# 09_Misc.net
KiCad netlist of a schematic drawn in Altium Designer
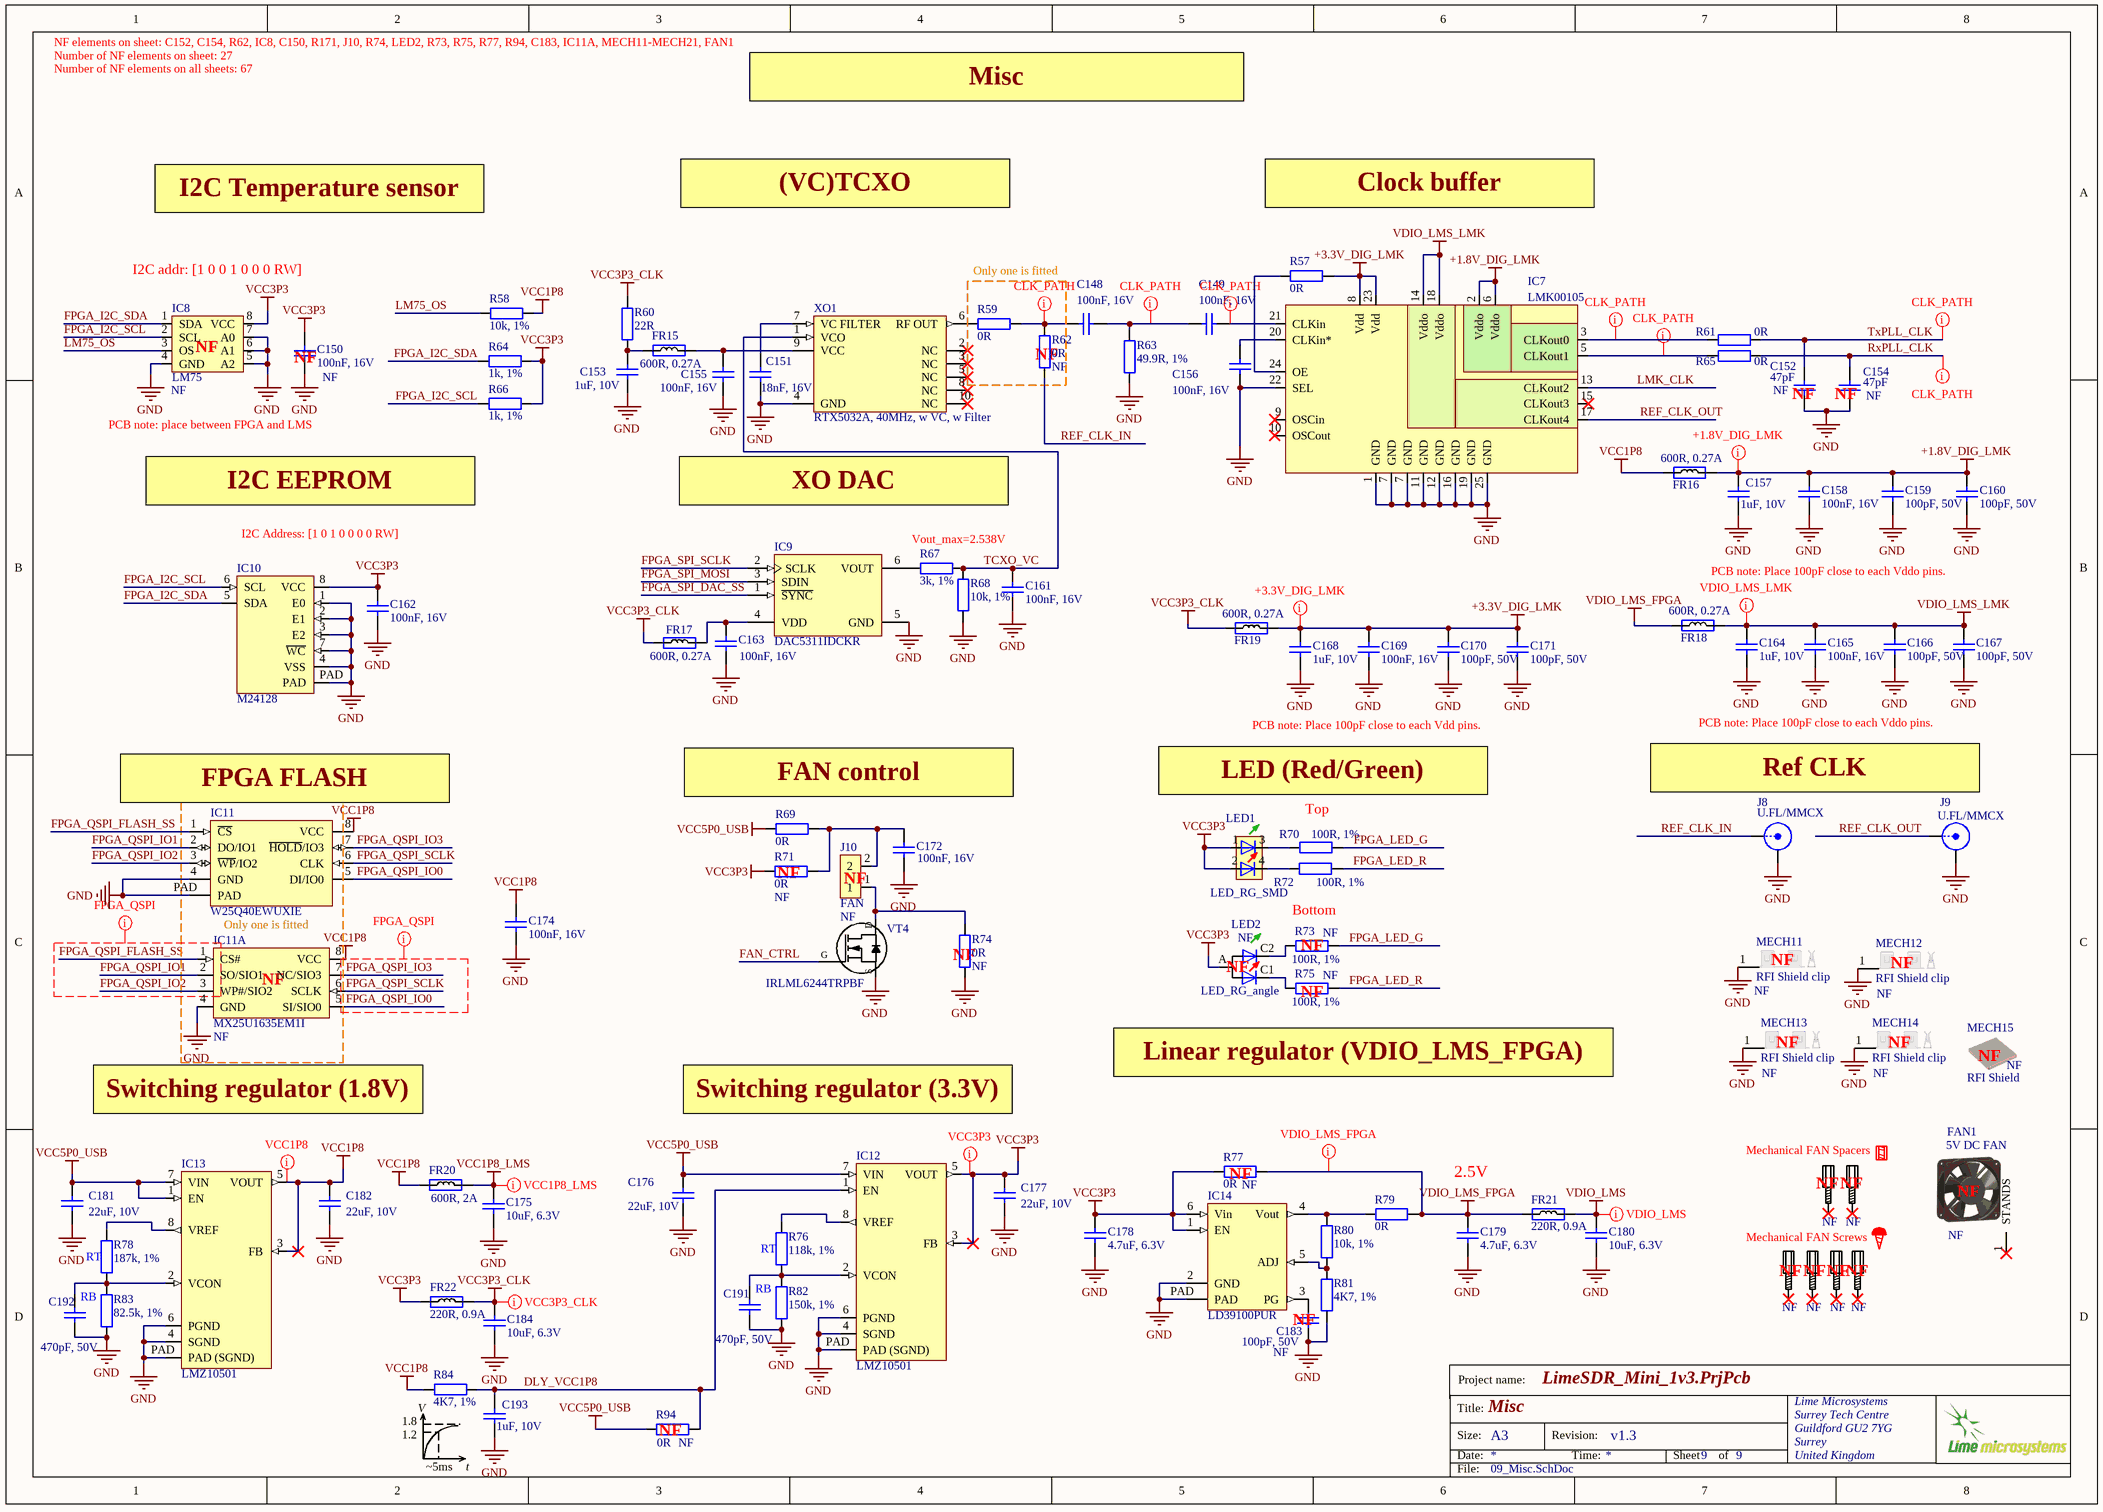
[diagram p0: 09_Misc.SchDoc]

(export (version "E")
  (design (tool "Eeschema 10.0.6"))
  (components
    (comp (ref "C148")
      (value "100nF, 16V")
      (footprint "CAP0402")
      (fields
        (field (name "MANUFACTURER") "Murata Electronics")
        (field (name "TOLERANCE") "10 %")
        (field (name "MANUFACTURER PART NUMBER") "GRM155R71C104KA88D")
      )
      (libsource (lib "LimeMicroAltiumLib_schLib") (part "Cap_0402"))
    )
    (comp (ref "C149")
      (value "100nF, 16V")
      (footprint "CAP0402")
      (fields
        (field (name "MANUFACTURER") "Murata Electronics")
        (field (name "TOLERANCE") "10 %")
        (field (name "MANUFACTURER PART NUMBER") "GRM155R71C104KA88D")
      )
      (libsource (lib "LimeMicroAltiumLib_schLib") (part "Cap_0402"))
    )
    (comp (ref "C150")
      (value "100nF, 16V")
      (footprint "CAP0402")
      (fields
        (field (name "TOLERANCE") "10 %")
        (field (name "MANUFACTURER") "Murata Electronics")
        (field (name "MANUFACTURER PART NUMBER") "GRM155R71C104KA88D")
        (field (name "ASSEMBLY INFO") "NF")
      )
      (libsource (lib "LimeFPGAboard_schLib") (part "Cap_0603"))
    )
    (comp (ref "C151")
      (value "18nF, 16V")
      (footprint "CAP0402")
      (fields (field (name "MANUFACTURER") "Yageo") (field (name "TOLERANCE") "±10%"))
      (libsource (lib "LimeMicroAltiumLib_schLib") (part "Cap_0402"))
    )
    (comp (ref "C152")
      (value "47pF")
      (footprint "CAP0402")
      (fields
        (field (name "TOLERANCE") "±1%")
        (field (name "MANUFACTURER") "TDK Corporation")
        (field (name "ASSEMBLY INFO") "NF")
      )
      (libsource (lib "LimeMicroAltiumLib_schLib") (part "Cap_0402"))
    )
    (comp (ref "C153")
      (value "1uF, 10V")
      (footprint "CAP0402")
      (fields (field (name "MANUFACTURER") "TDK"))
      (libsource (lib "LimeMicroAltiumLib_schLib") (part "Cap_0402"))
    )
    (comp (ref "C154")
      (value "47pF")
      (footprint "CAP0402")
      (fields
        (field (name "TOLERANCE") "±1%")
        (field (name "MANUFACTURER") "TDK Corporation")
        (field (name "ASSEMBLY INFO") "NF")
      )
      (libsource (lib "LimeMicroAltiumLib_schLib") (part "Cap_0402"))
    )
    (comp (ref "C155")
      (value "100nF, 16V")
      (footprint "CAP0402")
      (fields
        (field (name "MANUFACTURER") "Murata Electronics")
        (field (name "TOLERANCE") "10 %")
        (field (name "MANUFACTURER PART NUMBER") "GRM155R71C104KA88D")
      )
      (libsource (lib "LimeMicroAltiumLib_schLib") (part "Cap_0402"))
    )
    (comp (ref "C156")
      (value "100nF, 16V")
      (footprint "CAP0402")
      (fields
        (field (name "MANUFACTURER") "Murata Electronics")
        (field (name "TOLERANCE") "10 %")
        (field (name "MANUFACTURER PART NUMBER") "GRM155R71C104KA88D")
      )
      (libsource (lib "LimeMicroAltiumLib_schLib") (part "Cap_0402"))
    )
    (comp (ref "C157")
      (value "1uF, 10V")
      (footprint "CAP0402")
      (fields (field (name "MANUFACTURER") "TDK"))
      (libsource (lib "LimeMicroAltiumLib_schLib") (part "Cap_0402"))
    )
    (comp (ref "C158")
      (value "100nF, 16V")
      (footprint "CAP0402")
      (fields
        (field (name "MANUFACTURER") "Murata Electronics")
        (field (name "TOLERANCE") "10 %")
        (field (name "MANUFACTURER PART NUMBER") "GRM155R71C104KA88D")
      )
      (libsource (lib "LimeMicroAltiumLib_schLib") (part "Cap_0402"))
    )
    (comp (ref "C159")
      (value "100pF, 50V")
      (footprint "CAP0402")
      (fields (field (name "MANUFACTURER") "Yageo") (field (name "TOLERANCE") "±5%"))
      (libsource (lib "LimeMicroAltiumLib_schLib") (part "Cap_0402"))
    )
    (comp (ref "C160")
      (value "100pF, 50V")
      (footprint "CAP0402")
      (fields (field (name "MANUFACTURER") "Yageo") (field (name "TOLERANCE") "±5%"))
      (libsource (lib "LimeMicroAltiumLib_schLib") (part "Cap_0402"))
    )
    (comp (ref "C161")
      (value "100nF, 16V")
      (footprint "CAP0402")
      (fields
        (field (name "MANUFACTURER") "Murata Electronics")
        (field (name "TOLERANCE") "10 %")
        (field (name "MANUFACTURER PART NUMBER") "GRM155R71C104KA88D")
      )
      (libsource (lib "LimeMicroAltiumLib_schLib") (part "Cap_0402"))
    )
    (comp (ref "C162")
      (value "100nF, 16V")
      (footprint "CAP0402")
      (fields
        (field (name "TOLERANCE") "10 %")
        (field (name "MANUFACTURER") "Murata Electronics")
        (field (name "MANUFACTURER PART NUMBER") "GRM155R71C104KA88D")
      )
      (libsource (lib "LimeFPGAboard_schLib") (part "Cap_0603"))
    )
    (comp (ref "C163")
      (value "100nF, 16V")
      (footprint "CAP0402")
      (fields
        (field (name "TOLERANCE") "10 %")
        (field (name "MANUFACTURER") "Murata Electronics")
        (field (name "MANUFACTURER PART NUMBER") "GRM155R71C104KA88D")
      )
      (libsource (lib "LimeFPGAboard_schLib") (part "Cap_0603"))
    )
    (comp (ref "C164")
      (value "1uF, 10V")
      (footprint "CAP0402")
      (fields (field (name "MANUFACTURER") "TDK"))
      (libsource (lib "LimeMicroAltiumLib_schLib") (part "Cap_0402"))
    )
    (comp (ref "C165")
      (value "100nF, 16V")
      (footprint "CAP0402")
      (fields
        (field (name "MANUFACTURER") "Murata Electronics")
        (field (name "TOLERANCE") "10 %")
        (field (name "MANUFACTURER PART NUMBER") "GRM155R71C104KA88D")
      )
      (libsource (lib "LimeMicroAltiumLib_schLib") (part "Cap_0402"))
    )
    (comp (ref "C166")
      (value "100pF, 50V")
      (footprint "CAP0402")
      (fields (field (name "MANUFACTURER") "Yageo") (field (name "TOLERANCE") "±5%"))
      (libsource (lib "LimeMicroAltiumLib_schLib") (part "Cap_0402"))
    )
    (comp (ref "C167")
      (value "100pF, 50V")
      (footprint "CAP0402")
      (fields (field (name "MANUFACTURER") "Yageo") (field (name "TOLERANCE") "±5%"))
      (libsource (lib "LimeMicroAltiumLib_schLib") (part "Cap_0402"))
    )
    (comp (ref "C168")
      (value "1uF, 10V")
      (footprint "CAP0402")
      (fields (field (name "MANUFACTURER") "TDK"))
      (libsource (lib "LimeMicroAltiumLib_schLib") (part "Cap_0402"))
    )
    (comp (ref "C169")
      (value "100nF, 16V")
      (footprint "CAP0402")
      (fields
        (field (name "MANUFACTURER") "Murata Electronics")
        (field (name "TOLERANCE") "10 %")
        (field (name "MANUFACTURER PART NUMBER") "GRM155R71C104KA88D")
      )
      (libsource (lib "LimeMicroAltiumLib_schLib") (part "Cap_0402"))
    )
    (comp (ref "C170")
      (value "100pF, 50V")
      (footprint "CAP0402")
      (fields (field (name "MANUFACTURER") "Yageo") (field (name "TOLERANCE") "±5%"))
      (libsource (lib "LimeMicroAltiumLib_schLib") (part "Cap_0402"))
    )
    (comp (ref "C171")
      (value "100pF, 50V")
      (footprint "CAP0402")
      (fields (field (name "MANUFACTURER") "Yageo") (field (name "TOLERANCE") "±5%"))
      (libsource (lib "LimeMicroAltiumLib_schLib") (part "Cap_0402"))
    )
    (comp (ref "C172")
      (value "100nF, 16V")
      (footprint "CAP0402")
      (fields
        (field (name "TOLERANCE") "10 %")
        (field (name "MANUFACTURER") "Murata Electronics")
        (field (name "MANUFACTURER PART NUMBER") "GRM155R71C104KA88D")
      )
      (libsource (lib "LimeFPGAboard_schLib") (part "Cap_0603"))
    )
    (comp (ref "C174")
      (value "100nF, 16V")
      (footprint "CAP0402")
      (fields
        (field (name "TOLERANCE") "10 %")
        (field (name "MANUFACTURER") "Murata Electronics")
        (field (name "MANUFACTURER PART NUMBER") "GRM155R71C104KA88D")
      )
      (libsource (lib "LimeFPGAboard_schLib") (part "Cap_0603"))
    )
    (comp (ref "C175")
      (value "10uF, 6.3V")
      (footprint "CAP0603")
      (fields (field (name "TOLERANCE") "±20%") (field (name "MANUFACTURER") "Yageo"))
      (libsource (lib "LimeFPGAboard_schLib") (part "Cap_0603"))
    )
    (comp (ref "C176")
      (value "22uF, 10V")
      (footprint "CAP0603")
      (fields (field (name "TOLERANCE") "20 %") (field (name "MANUFACTURER") "TDK Corporation"))
      (libsource (lib "LimeFPGAboard_schLib") (part "Cap_0603"))
    )
    (comp (ref "C177")
      (value "22uF, 10V")
      (footprint "CAP0603")
      (fields (field (name "TOLERANCE") "20 %") (field (name "MANUFACTURER") "TDK Corporation"))
      (libsource (lib "LimeFPGAboard_schLib") (part "Cap_0603"))
    )
    (comp (ref "C178")
      (value "4.7uF, 6.3V")
      (footprint "CAP0402")
      (fields
        (field (name "MANUFACTURER") "Murata Electronics North America")
        (field (name "TOLERANCE") "±20%")
      )
      (libsource (lib "LimeMicroAltiumLib_schLib") (part "Cap_0402"))
    )
    (comp (ref "C179")
      (value "4.7uF, 6.3V")
      (footprint "CAP0402")
      (fields
        (field (name "MANUFACTURER") "Murata Electronics North America")
        (field (name "TOLERANCE") "±20%")
      )
      (libsource (lib "LimeMicroAltiumLib_schLib") (part "Cap_0402"))
    )
    (comp (ref "C180")
      (value "10uF, 6.3V")
      (footprint "CAP0603")
      (fields (field (name "TOLERANCE") "±20%") (field (name "MANUFACTURER") "Yageo"))
      (libsource (lib "LimeFPGAboard_schLib") (part "Cap_0603"))
    )
    (comp (ref "C181")
      (value "22uF, 10V")
      (footprint "CAP0603")
      (fields (field (name "TOLERANCE") "20 %") (field (name "MANUFACTURER") "TDK Corporation"))
      (libsource (lib "LimeFPGAboard_schLib") (part "Cap_0603"))
    )
    (comp (ref "C182")
      (value "22uF, 10V")
      (footprint "CAP0603")
      (fields (field (name "TOLERANCE") "20 %") (field (name "MANUFACTURER") "TDK Corporation"))
      (libsource (lib "LimeFPGAboard_schLib") (part "Cap_0603"))
    )
    (comp (ref "C183")
      (value "100pF, 50V")
      (footprint "CAP0402")
      (fields
        (field (name "ASSEMBLY INFO") "NF")
        (field (name "MANUFACTURER") "Yageo")
        (field (name "TOLERANCE") "±5%")
      )
      (libsource (lib "LimeMicroAltiumLib_schLib") (part "Cap_0402"))
    )
    (comp (ref "C184")
      (value "10uF, 6.3V")
      (footprint "CAP0603")
      (fields (field (name "TOLERANCE") "±20%") (field (name "MANUFACTURER") "Yageo"))
      (libsource (lib "LimeFPGAboard_schLib") (part "Cap_0603"))
    )
    (comp (ref "C191")
      (value "470pF, 50V")
      (footprint "CAP0402")
      (fields (field (name "TOLERANCE") "±5%") (field (name "MANUFACTURER") "TDK Corporation"))
      (libsource (lib "LimeMicroAltiumLib_schLib") (part "Cap_0402"))
    )
    (comp (ref "C192")
      (value "470pF, 50V")
      (footprint "CAP0402")
      (fields (field (name "TOLERANCE") "±5%") (field (name "MANUFACTURER") "TDK Corporation"))
      (libsource (lib "LimeMicroAltiumLib_schLib") (part "Cap_0402"))
    )
    (comp (ref "C193")
      (value "1uF, 10V")
      (footprint "CAP0402")
      (fields (field (name "MANUFACTURER") "TDK"))
      (libsource (lib "LimeMicroAltiumLib_schLib") (part "Cap_0402"))
    )
    (comp (ref "FAN1")
      (value "5V DC FAN")
      (fields (field (name "MANUFACTURER") "Sunon Fans") (field (name "ASSEMBLY INFO") "NF"))
      (libsource (lib "LimeMicroAltiumLib_schLib") (part "12V_DC_FAN"))
    )
    (comp (ref "FR15")
      (value "600R, 0.27A")
      (footprint "RES0201")
      (fields (field (name "MANUFACTURER") "Taiyo Yuden"))
      (libsource (lib "LimeMicroAltiumLib_schLib") (part "Ferrite"))
    )
    (comp (ref "FR16")
      (value "600R, 0.27A")
      (footprint "RES0201")
      (fields (field (name "MANUFACTURER") "Taiyo Yuden"))
      (libsource (lib "LimeMicroAltiumLib_schLib") (part "Ferrite"))
    )
    (comp (ref "FR17")
      (value "600R, 0.27A")
      (footprint "RES0201")
      (fields (field (name "MANUFACTURER") "Taiyo Yuden"))
      (libsource (lib "LimeMicroAltiumLib_schLib") (part "Ferrite"))
    )
    (comp (ref "FR18")
      (value "600R, 0.27A")
      (footprint "RES0201")
      (fields (field (name "MANUFACTURER") "Taiyo Yuden"))
      (libsource (lib "LimeMicroAltiumLib_schLib") (part "Ferrite"))
    )
    (comp (ref "FR19")
      (value "600R, 0.27A")
      (footprint "RES0201")
      (fields (field (name "MANUFACTURER") "Taiyo Yuden"))
      (libsource (lib "LimeMicroAltiumLib_schLib") (part "Ferrite"))
    )
    (comp (ref "FR20")
      (value "600R, 2A")
      (footprint "RES0805")
      (fields (field (name "MANUFACTURER") "TDK Corporation"))
      (libsource (lib "LimeMicroAltiumLib_schLib") (part "Ferrite"))
    )
    (comp (ref "FR21")
      (value "220R, 0.9A")
      (footprint "RES0402")
      (fields (field (name "MANUFACTURER") "TDK Corporation"))
      (libsource (lib "LimeFPGAboard_schLib") (part "Ferrite"))
    )
    (comp (ref "FR22")
      (value "220R, 0.9A")
      (footprint "RES0402")
      (fields (field (name "MANUFACTURER") "TDK Corporation"))
      (libsource (lib "LimeFPGAboard_schLib") (part "Ferrite"))
    )
    (comp (ref "IC7")
      (value "LMK00105")
      (footprint "LMK00105SQ")
      (fields (field (name "MANUFACTURER") "Texas Instruments"))
      (libsource (lib "LimeMicroAltiumLib_schLib") (part "LMK00105"))
    )
    (comp (ref "IC8")
      (value "LM75")
      (footprint "HWSON8_LM75")
      (fields (field (name "MANUFACTURER") "NXP Semiconductors") (field (name "ASSEMBLY INFO") "NF"))
      (libsource (lib "LimeMicroAltiumLib_schLib") (part "LM75"))
    )
    (comp (ref "IC9")
      (value "DAC5311IDCKR")
      (footprint "AD5601_SOT23-6")
      (fields (field (name "MANUFACTURER") "Texas Instruments"))
      (libsource (lib "LimeMicroAltiumLib_schLib") (part "AD5601BKSZ-REEL7"))
    )
    (comp (ref "IC10")
      (value "M24128")
      (footprint "M24128-DFMC6TG")
      (fields (field (name "MANUFACTURER") "STMicroelectronics"))
      (libsource (lib "LimeMicroAltiumLib_schLib") (part "M24128-DFMC6TG"))
    )
    (comp (ref "IC11")
      (value "W25Q40EWUXIE")
      (footprint "W25Q40EWUXIE_8-USON")
      (fields (field (name "MANUFACTURER") "Winbond Electronics"))
      (libsource (lib "LimeMicroAltiumLib_schLib") (part "W25Q40EWUXIE"))
    )
    (comp (ref "IC11A")
      (value "MX25U1635EM1I")
      (footprint "MX25U1635EM1I-10G_SOP8_150mil")
      (fields (field (name "MANUFACTURER") "Macronix") (field (name "ASSEMBLY INFO") "NF"))
      (libsource (lib "LimeMicroAltiumLib_schLib") (part "MX25U1635EM1I-10G"))
    )
    (comp (ref "IC12")
      (value "LMZ10501")
      (footprint "LMZ10501")
      (fields (field (name "MANUFACTURER") "Texas Instruments"))
      (libsource (lib "LimeMicroAltiumLib_schLib") (part "LMZ10501"))
    )
    (comp (ref "IC13")
      (value "LMZ10501")
      (footprint "LMZ10501")
      (fields (field (name "MANUFACTURER") "Texas Instruments"))
      (libsource (lib "LimeMicroAltiumLib_schLib") (part "LMZ10501"))
    )
    (comp (ref "IC14")
      (value "LD39100PUR")
      (footprint "LD39100PUR")
      (fields (field (name "MANUFACTURER") "STMicroelectronics"))
      (libsource (lib "LimeMicroAltiumLib_schLib") (part "LD39100PUR"))
    )
    (comp (ref "J8")
      (value "U.FL/MMCX")
      (footprint "MMCX_UFL_conn_u")
      (description "CONN UMC RCPT STR 50 OHM SMD")
      (fields (field (name "MANUFACTURER") "Molex, LLC"))
      (libsource (lib "LimeMicroAltiumLib_schLib") (part "RF_IF_connector"))
    )
    (comp (ref "J9")
      (value "U.FL/MMCX")
      (footprint "MMCX_UFL_conn_u")
      (description "CONN UMC RCPT STR 50 OHM SMD")
      (fields (field (name "MANUFACTURER") "Molex, LLC"))
      (libsource (lib "LimeMicroAltiumLib_schLib") (part "RF_IF_connector"))
    )
    (comp (ref "J10")
      (value "FAN")
      (footprint "Header2x1_TH_v2")
      (fields (field (name "ASSEMBLY INFO") "NF") (field (name "MANUFACTURER") "3M"))
      (libsource (lib "LimeFPGAboard_schLib") (part "Jumper"))
    )
    (comp (ref "LED1")
      (value "LED_RG_SMD")
      (footprint "LED-2x0603")
      (fields (field (name "MANUFACTURER") "Avago Technologies US Inc."))
      (libsource (lib "LimeMicroAltiumLib_schLib") (part "LED_green_red_SMD"))
    )
    (comp (ref "LED2")
      (value "LED_RG_angle")
      (footprint "LED_RG_RIGHT_ANGLE_v2")
      (description "160-2033-1-ND")
      (fields (field (name "MANUFACTURER") "Lite-On") (field (name "ASSEMBLY INFO") "NF"))
      (libsource (lib "LimeMicroAltiumLib_schLib") (part "LED_green_red_right_angle"))
    )
    (comp (ref "MECH11")
      (value "RFI Shield clip")
      (footprint "RFI_SHIELD_CLPS_MINI")
      (fields (field (name "MANUFACTURER") "HARWIN") (field (name "ASSEMBLY INFO") "NF"))
      (libsource (lib "LimeMicroAltiumLib_schLib") (part "RFI_SHIELD_CLIP"))
    )
    (comp (ref "MECH12")
      (value "RFI Shield clip")
      (footprint "RFI_SHIELD_CLPS_MINI")
      (fields (field (name "MANUFACTURER") "HARWIN") (field (name "ASSEMBLY INFO") "NF"))
      (libsource (lib "LimeMicroAltiumLib_schLib") (part "RFI_SHIELD_CLIP"))
    )
    (comp (ref "MECH13")
      (value "RFI Shield clip")
      (footprint "RFI_SHIELD_CLPS_MINI")
      (fields (field (name "MANUFACTURER") "HARWIN") (field (name "ASSEMBLY INFO") "NF"))
      (libsource (lib "LimeMicroAltiumLib_schLib") (part "RFI_SHIELD_CLIP"))
    )
    (comp (ref "MECH14")
      (value "RFI Shield clip")
      (footprint "RFI_SHIELD_CLPS_MINI")
      (fields (field (name "MANUFACTURER") "HARWIN") (field (name "ASSEMBLY INFO") "NF"))
      (libsource (lib "LimeMicroAltiumLib_schLib") (part "RFI_SHIELD_CLIP"))
    )
    (comp (ref "MECH15")
      (value "RFI Shield")
      (footprint "WurthElectronic_RF_shield")
      (fields (field (name "MANUFACTURER") "WURTH ELEKTRONIK") (field (name "ASSEMBLY INFO") "NF"))
      (libsource (lib "LimeMicroAltiumLib_schLib") (part "RFI_SHIELD_1"))
    )
    (comp (ref "MECH16")
      (value "Spacer M3")
      (description "STANDOFF M/F MET 5MM HEX 10MM L")
      (fields (field (name "MANUFACTURER") "BOSSARD") (field (name "ASSEMBLY INFO") "NF"))
      (libsource (lib "LimeMicroAltiumLib_schLib") (part "STANDOFF_M-F_THREADED_M3x8x10mm_HEX_5mm dia"))
    )
    (comp (ref "MECH17")
      (value "Spacer M3")
      (description "STANDOFF M/F MET 5MM HEX 10MM L")
      (fields (field (name "MANUFACTURER") "BOSSARD") (field (name "ASSEMBLY INFO") "NF"))
      (libsource (lib "LimeMicroAltiumLib_schLib") (part "STANDOFF_M-F_THREADED_M3x8x10mm_HEX_5mm dia"))
    )
    (comp (ref "MECH18")
      (value "Screws M3")
      (description "STANDOFF M/F MET 5MM HEX 10MM L")
      (fields (field (name "MANUFACTURER") "KRAFTBERG") (field (name "ASSEMBLY INFO") "NF"))
      (libsource (lib "LimeMicroAltiumLib_schLib") (part "STANDOFF_M-F_THREADED_M3x8x10mm_HEX_5mm dia"))
    )
    (comp (ref "MECH19")
      (value "Screws M3")
      (description "STANDOFF M/F MET 5MM HEX 10MM L")
      (fields (field (name "MANUFACTURER") "KRAFTBERG") (field (name "ASSEMBLY INFO") "NF"))
      (libsource (lib "LimeMicroAltiumLib_schLib") (part "STANDOFF_M-F_THREADED_M3x8x10mm_HEX_5mm dia"))
    )
    (comp (ref "MECH20")
      (value "Screws M3")
      (description "STANDOFF M/F MET 5MM HEX 10MM L")
      (fields (field (name "MANUFACTURER") "KRAFTBERG") (field (name "ASSEMBLY INFO") "NF"))
      (libsource (lib "LimeMicroAltiumLib_schLib") (part "STANDOFF_M-F_THREADED_M3x8x10mm_HEX_5mm dia"))
    )
    (comp (ref "MECH21")
      (value "Screws M3")
      (description "STANDOFF M/F MET 5MM HEX 10MM L")
      (fields (field (name "MANUFACTURER") "KRAFTBERG") (field (name "ASSEMBLY INFO") "NF"))
      (libsource (lib "LimeMicroAltiumLib_schLib") (part "STANDOFF_M-F_THREADED_M3x8x10mm_HEX_5mm dia"))
    )
    (comp (ref "R57")
      (value "0R")
      (footprint "RES0402")
      (fields (field (name "MANUFACTURER") "Yageo") (field (name "TOLERANCE") "Jumper"))
      (libsource (lib "LimeMicroAltiumLib_schLib") (part "Res_0402"))
    )
    (comp (ref "R58")
      (value "10k, 1%")
      (footprint "RES0402")
      (fields (field (name "MANUFACTURER") "Yageo") (field (name "TOLERANCE") "±1%"))
      (libsource (lib "LimeMicroAltiumLib_schLib") (part "Res_0402"))
    )
    (comp (ref "R59")
      (value "0R")
      (footprint "RES0402")
      (fields (field (name "MANUFACTURER") "Yageo") (field (name "TOLERANCE") "Jumper"))
      (libsource (lib "LimeMicroAltiumLib_schLib") (part "Res_0402"))
    )
    (comp (ref "R60")
      (value "22R")
      (footprint "RES0402")
      (fields (field (name "TOLERANCE") "±1%") (field (name "MANUFACTURER") "Yageo"))
      (libsource (lib "LimeFPGAboard_schLib") (part "Res_0402"))
    )
    (comp (ref "R61")
      (value "0R")
      (footprint "RES0402")
      (fields (field (name "MANUFACTURER") "Yageo"))
      (libsource (lib "LimeFPGAboard_schLib") (part "Res_0402"))
    )
    (comp (ref "R62")
      (value "0R")
      (footprint "RES0402")
      (fields
        (field (name "ASSEMBLY INFO") "NF")
        (field (name "MANUFACTURER") "Yageo")
        (field (name "TOLERANCE") "Jumper")
      )
      (libsource (lib "LimeMicroAltiumLib_schLib") (part "Res_0402"))
    )
    (comp (ref "R63")
      (value "49.9R, 1%")
      (footprint "RES0402")
      (fields
        (field (name "TOLERANCE") "±1%")
        (field (name "MANUFACTURER") "Samsung Electro-Mechanics America, Inc.")
      )
      (libsource (lib "LimeMicroAltiumLib_schLib") (part "Res_0402"))
    )
    (comp (ref "R64")
      (value "1k, 1%")
      (footprint "RES0402")
      (fields (field (name "MANUFACTURER") "Stackpole Electronics Inc") (field (name "TOLERANCE") "±1%"))
      (libsource (lib "LimeMicroAltiumLib_schLib") (part "Res_0402"))
    )
    (comp (ref "R65")
      (value "0R")
      (footprint "RES0402")
      (fields (field (name "MANUFACTURER") "Yageo"))
      (libsource (lib "LimeFPGAboard_schLib") (part "Res_0402"))
    )
    (comp (ref "R66")
      (value "1k, 1%")
      (footprint "RES0402")
      (fields (field (name "MANUFACTURER") "Stackpole Electronics Inc") (field (name "TOLERANCE") "±1%"))
      (libsource (lib "LimeMicroAltiumLib_schLib") (part "Res_0402"))
    )
    (comp (ref "R67")
      (value "3k, 1%")
      (footprint "RES0402")
      (fields (field (name "TOLERANCE") "±1%") (field (name "MANUFACTURER") "Vishay Dale"))
      (libsource (lib "LimeMicroAltiumLib_schLib") (part "Res_0402"))
    )
    (comp (ref "R68")
      (value "10k, 1%")
      (footprint "RES0402")
      (fields (field (name "MANUFACTURER") "Yageo") (field (name "TOLERANCE") "±1%"))
      (libsource (lib "LimeMicroAltiumLib_schLib") (part "Res_0402"))
    )
    (comp (ref "R69")
      (value "0R")
      (footprint "RES0402")
      (fields (field (name "MANUFACTURER") "Yageo") (field (name "TOLERANCE") "Jumper"))
      (libsource (lib "LimeMicroAltiumLib_schLib") (part "Res_0402"))
    )
    (comp (ref "R70")
      (value "100R, 1%")
      (footprint "RES0402")
      (fields (field (name "TOLERANCE") "±1%") (field (name "MANUFACTURER") "Stackpole Electronics Inc."))
      (libsource (lib "LimeMicroAltiumLib_schLib") (part "Res_0402"))
    )
    (comp (ref "R71")
      (value "0R")
      (footprint "RES0402")
      (fields
        (field (name "ASSEMBLY INFO") "NF")
        (field (name "MANUFACTURER") "Yageo")
        (field (name "TOLERANCE") "Jumper")
      )
      (libsource (lib "LimeMicroAltiumLib_schLib") (part "Res_0402"))
    )
    (comp (ref "R72")
      (value "100R, 1%")
      (footprint "RES0402")
      (fields (field (name "TOLERANCE") "±1%") (field (name "MANUFACTURER") "Stackpole Electronics Inc."))
      (libsource (lib "LimeMicroAltiumLib_schLib") (part "Res_0402"))
    )
    (comp (ref "R73")
      (value "100R, 1%")
      (footprint "RES0402")
      (fields
        (field (name "TOLERANCE") "±1%")
        (field (name "MANUFACTURER") "Stackpole Electronics Inc.")
        (field (name "ASSEMBLY INFO") "NF")
      )
      (libsource (lib "LimeMicroAltiumLib_schLib") (part "Res_0402"))
    )
    (comp (ref "R74")
      (value "0R")
      (footprint "RES0402")
      (fields
        (field (name "ASSEMBLY INFO") "NF")
        (field (name "MANUFACTURER") "Yageo")
        (field (name "TOLERANCE") "Jumper")
      )
      (libsource (lib "LimeMicroAltiumLib_schLib") (part "Res_0402"))
    )
    (comp (ref "R75")
      (value "100R, 1%")
      (footprint "RES0402")
      (fields
        (field (name "TOLERANCE") "±1%")
        (field (name "MANUFACTURER") "Stackpole Electronics Inc.")
        (field (name "ASSEMBLY INFO") "NF")
      )
      (libsource (lib "LimeMicroAltiumLib_schLib") (part "Res_0402"))
    )
    (comp (ref "R76")
      (value "118k, 1%")
      (footprint "RES0402")
      (fields (field (name "MANUFACTURER") "Yageo") (field (name "TOLERANCE") "±1%"))
      (libsource (lib "LimeMicroAltiumLib_schLib") (part "Res_0402"))
    )
    (comp (ref "R77")
      (value "0R")
      (footprint "RES0402")
      (fields (field (name "MANUFACTURER") "Yageo") (field (name "ASSEMBLY INFO") "NF"))
      (libsource (lib "LimeFPGAboard_schLib") (part "Res_0402"))
    )
    (comp (ref "R78")
      (value "187k, 1%")
      (footprint "RES0402")
      (fields (field (name "TOLERANCE") "±1%") (field (name "MANUFACTURER") "Yageo"))
      (libsource (lib "LimeMicroAltiumLib_schLib") (part "Res_0402"))
    )
    (comp (ref "R79")
      (value "0R")
      (footprint "RES0402")
      (fields (field (name "MANUFACTURER") "Yageo"))
      (libsource (lib "LimeFPGAboard_schLib") (part "Res_0402"))
    )
    (comp (ref "R80")
      (value "10k, 1%")
      (footprint "RES0402")
      (fields (field (name "MANUFACTURER") "Yageo") (field (name "TOLERANCE") "±1%"))
      (libsource (lib "LimeMicroAltiumLib_schLib") (part "Res_0402"))
    )
    (comp (ref "R81")
      (value "4K7, 1%")
      (footprint "RES0402")
      (fields (field (name "MANUFACTURER") "Yageo") (field (name "TOLERANCE") "±1%"))
      (libsource (lib "LimeFPGAboard_schLib") (part "Res_0402"))
    )
    (comp (ref "R82")
      (value "150k, 1%")
      (footprint "RES0402")
      (fields (field (name "TOLERANCE") "±5%") (field (name "MANUFACTURER") "Yageo"))
      (libsource (lib "LimeMicroAltiumLib_schLib") (part "Res_0402"))
    )
    (comp (ref "R83")
      (value "82.5k, 1%")
      (footprint "RES0402")
      (fields (field (name "TOLERANCE") "±1%") (field (name "MANUFACTURER") "Yageo"))
      (libsource (lib "LimeMicroAltiumLib_schLib") (part "Res_0402"))
    )
    (comp (ref "R84")
      (value "4K7, 1%")
      (footprint "RES0402")
      (fields (field (name "MANUFACTURER") "Yageo") (field (name "TOLERANCE") "±1%"))
      (libsource (lib "LimeFPGAboard_schLib") (part "Res_0402"))
    )
    (comp (ref "R94")
      (value "0R")
      (footprint "RES0402")
      (fields
        (field (name "ASSEMBLY INFO") "NF")
        (field (name "MANUFACTURER") "Yageo")
        (field (name "TOLERANCE") "Jumper")
      )
      (libsource (lib "LimeMicroAltiumLib_schLib") (part "Res_0402"))
    )
    (comp (ref "VT4")
      (value "IRLML6244TRPBF")
      (footprint "SOT23-3")
      (description "NDS331N")
      (fields (field (name "MANUFACTURER") "Infineon Technologies"))
      (libsource (lib "LimeFPGAboard_schLib") (part "NDS331N"))
    )
    (comp (ref "XO1")
      (value "RTX5032A, 40MHz, w VC, w Filter")
      (footprint "RAKON_RTX5032A")
      (fields (field (name "MANUFACTURER") "Rakon"))
      (libsource (lib "LimeMicroAltiumLib_schLib") (part "Rakon_RTX5032A"))
    )
  )
  (nets
    (net (code "1") (name "+1.8V_DIG_LMK") (class "Default")
      (node (ref "C157") (pin "2") (pinfunction "2_2") (pintype "passive"))
      (node (ref "C158") (pin "2") (pinfunction "2_2") (pintype "passive"))
      (node (ref "C159") (pin "2") (pinfunction "2_2") (pintype "passive"))
      (node (ref "C160") (pin "2") (pinfunction "2_2") (pintype "passive"))
      (node (ref "FR16") (pin "2") (pinfunction "2_2") (pintype "passive"))
      (node (ref "IC7") (pin "2") (pinfunction "Vddo_2") (pintype "passive"))
      (node (ref "IC7") (pin "6") (pinfunction "Vddo_6") (pintype "passive"))
    )
    (net (code "2") (name "+3.3V_DIG_LMK") (class "Default")
      (node (ref "C168") (pin "2") (pinfunction "2_2") (pintype "passive"))
      (node (ref "C169") (pin "2") (pinfunction "2_2") (pintype "passive"))
      (node (ref "C170") (pin "2") (pinfunction "2_2") (pintype "passive"))
      (node (ref "C171") (pin "2") (pinfunction "2_2") (pintype "passive"))
      (node (ref "FR19") (pin "2") (pinfunction "2_2") (pintype "passive"))
      (node (ref "IC7") (pin "23") (pinfunction "Vdd_23") (pintype "passive"))
      (node (ref "IC7") (pin "8") (pinfunction "Vdd_8") (pintype "passive"))
      (node (ref "R57") (pin "2") (pinfunction "2_2") (pintype "passive"))
    )
    (net (code "3") (name "/DLY_VCC1P8") (class "Default")
      (node (ref "C193") (pin "2") (pinfunction "2_2") (pintype "passive"))
      (node (ref "IC12") (pin "1") (pinfunction "EN_1") (pintype "input"))
      (node (ref "R84") (pin "1") (pinfunction "1_1") (pintype "passive"))
      (node (ref "R94") (pin "2") (pinfunction "2_2") (pintype "passive"))
    )
    (net (code "4") (name "/FAN_CTRL") (class "Default")
      (node (ref "VT4") (pin "G") (pinfunction "G_G") (pintype "passive"))
    )
    (net (code "5") (name "/FPGA_I2C_SCL") (class "Default")
      (node (ref "IC10") (pin "6") (pinfunction "SCL_6") (pintype "input"))
      (node (ref "IC8") (pin "2") (pinfunction "SCL_2") (pintype "passive"))
      (node (ref "R66") (pin "2") (pinfunction "2_2") (pintype "passive"))
    )
    (net (code "6") (name "/FPGA_I2C_SDA") (class "Default")
      (node (ref "IC10") (pin "5") (pinfunction "SDA_5") (pintype "bidirectional"))
      (node (ref "IC8") (pin "1") (pinfunction "SDA_1") (pintype "passive"))
      (node (ref "R64") (pin "2") (pinfunction "2_2") (pintype "passive"))
    )
    (net (code "7") (name "/FPGA_LED_G") (class "Default")
      (node (ref "R70") (pin "2") (pinfunction "2_2") (pintype "passive"))
      (node (ref "R73") (pin "2") (pinfunction "2_2") (pintype "passive"))
    )
    (net (code "8") (name "/FPGA_LED_R") (class "Default")
      (node (ref "R72") (pin "2") (pinfunction "2_2") (pintype "passive"))
      (node (ref "R75") (pin "2") (pinfunction "2_2") (pintype "passive"))
    )
    (net (code "9") (name "/FPGA_QSPI_FLASH_SS") (class "Default")
      (node (ref "IC11") (pin "1") (pinfunction "~{CS}_1") (pintype "input"))
      (node (ref "IC11A") (pin "1") (pinfunction "CS#_1") (pintype "input"))
    )
    (net (code "10") (name "/FPGA_QSPI_IO0") (class "Default")
      (node (ref "IC11") (pin "5") (pinfunction "DI/IO0_5") (pintype "passive"))
      (node (ref "IC11A") (pin "5") (pinfunction "SI/SIO0_5") (pintype "bidirectional"))
    )
    (net (code "11") (name "/FPGA_QSPI_IO1") (class "Default")
      (node (ref "IC11") (pin "2") (pinfunction "DO/IO1_2") (pintype "bidirectional"))
      (node (ref "IC11A") (pin "2") (pinfunction "SO/SIO1_2") (pintype "bidirectional"))
    )
    (net (code "12") (name "/FPGA_QSPI_IO2") (class "Default")
      (node (ref "IC11") (pin "3") (pinfunction "~{WP}/IO2_3") (pintype "bidirectional"))
      (node (ref "IC11A") (pin "3") (pinfunction "WP#/SIO2_3") (pintype "bidirectional"))
    )
    (net (code "13") (name "/FPGA_QSPI_IO3") (class "Default")
      (node (ref "IC11") (pin "7") (pinfunction "~{HOLD}/IO3_7") (pintype "bidirectional"))
      (node (ref "IC11A") (pin "7") (pinfunction "NC/SIO3_7") (pintype "bidirectional"))
    )
    (net (code "14") (name "/FPGA_QSPI_SCLK") (class "Default")
      (node (ref "IC11") (pin "6") (pinfunction "CLK_6") (pintype "input"))
      (node (ref "IC11A") (pin "6") (pinfunction "SCLK_6") (pintype "input"))
    )
    (net (code "15") (name "/FPGA_SPI_DAC_SS") (class "Default")
      (node (ref "IC9") (pin "1") (pinfunction "~{SYNC}_1") (pintype "input"))
    )
    (net (code "16") (name "/FPGA_SPI_MOSI") (class "Default")
      (node (ref "IC9") (pin "3") (pinfunction "SDIN_3") (pintype "input"))
    )
    (net (code "17") (name "/FPGA_SPI_SCLK") (class "Default")
      (node (ref "IC9") (pin "2") (pinfunction "SCLK_2") (pintype "input"))
    )
    (net (code "18") (name "/LM75_OS") (class "Default")
      (node (ref "IC8") (pin "3") (pinfunction "OS_3") (pintype "passive"))
      (node (ref "R58") (pin "1") (pinfunction "1_1") (pintype "passive"))
    )
    (net (code "19") (name "/LMK_CLK") (class "Default")
      (node (ref "IC7") (pin "13") (pinfunction "CLKout2_13") (pintype "passive"))
    )
    (net (code "20") (name "/REF_CLK_IN") (class "Default")
      (node (ref "J8") (pin "1") (pinfunction "X_1") (pintype "passive"))
      (node (ref "R62") (pin "1") (pinfunction "1_1") (pintype "passive"))
    )
    (net (code "21") (name "/REF_CLK_OUT") (class "Default")
      (node (ref "IC7") (pin "17") (pinfunction "CLKout4_17") (pintype "passive"))
      (node (ref "J9") (pin "1") (pinfunction "X_1") (pintype "passive"))
    )
    (net (code "22") (name "/RxPLL_CLK") (class "Default")
      (node (ref "C154") (pin "2") (pinfunction "2_2") (pintype "passive"))
      (node (ref "R65") (pin "1") (pinfunction "1_1") (pintype "passive"))
    )
    (net (code "23") (name "/TCXO_VC") (class "Default")
      (node (ref "C161") (pin "2") (pinfunction "2_2") (pintype "passive"))
      (node (ref "R67") (pin "1") (pinfunction "1_1") (pintype "passive"))
      (node (ref "R68") (pin "1") (pinfunction "1_1") (pintype "passive"))
      (node (ref "XO1") (pin "1") (pinfunction "VCO_1") (pintype "input"))
    )
    (net (code "24") (name "/TxPLL_CLK") (class "Default")
      (node (ref "C152") (pin "2") (pinfunction "2_2") (pintype "passive"))
      (node (ref "R61") (pin "1") (pinfunction "1_1") (pintype "passive"))
    )
    (net (code "25") (name "GND") (class "Default")
      (node (ref "C150") (pin "2") (pinfunction "2_2") (pintype "passive"))
      (node (ref "C151") (pin "1") (pinfunction "1_1") (pintype "passive"))
      (node (ref "C152") (pin "1") (pinfunction "1_1") (pintype "passive"))
      (node (ref "C153") (pin "1") (pinfunction "1_1") (pintype "passive"))
      (node (ref "C154") (pin "1") (pinfunction "1_1") (pintype "passive"))
      (node (ref "C155") (pin "1") (pinfunction "1_1") (pintype "passive"))
      (node (ref "C156") (pin "1") (pinfunction "1_1") (pintype "passive"))
      (node (ref "C157") (pin "1") (pinfunction "1_1") (pintype "passive"))
      (node (ref "C158") (pin "1") (pinfunction "1_1") (pintype "passive"))
      (node (ref "C159") (pin "1") (pinfunction "1_1") (pintype "passive"))
      (node (ref "C160") (pin "1") (pinfunction "1_1") (pintype "passive"))
      (node (ref "C161") (pin "1") (pinfunction "1_1") (pintype "passive"))
      (node (ref "C162") (pin "2") (pinfunction "2_2") (pintype "passive"))
      (node (ref "C163") (pin "2") (pinfunction "2_2") (pintype "passive"))
      (node (ref "C164") (pin "1") (pinfunction "1_1") (pintype "passive"))
      (node (ref "C165") (pin "1") (pinfunction "1_1") (pintype "passive"))
      (node (ref "C166") (pin "1") (pinfunction "1_1") (pintype "passive"))
      (node (ref "C167") (pin "1") (pinfunction "1_1") (pintype "passive"))
      (node (ref "C168") (pin "1") (pinfunction "1_1") (pintype "passive"))
      (node (ref "C169") (pin "1") (pinfunction "1_1") (pintype "passive"))
      (node (ref "C170") (pin "1") (pinfunction "1_1") (pintype "passive"))
      (node (ref "C171") (pin "1") (pinfunction "1_1") (pintype "passive"))
      (node (ref "C172") (pin "2") (pinfunction "2_2") (pintype "passive"))
      (node (ref "C174") (pin "2") (pinfunction "2_2") (pintype "passive"))
      (node (ref "C175") (pin "1") (pinfunction "1_1") (pintype "passive"))
      (node (ref "C176") (pin "1") (pinfunction "1_1") (pintype "passive"))
      (node (ref "C177") (pin "1") (pinfunction "1_1") (pintype "passive"))
      (node (ref "C178") (pin "1") (pinfunction "1_1") (pintype "passive"))
      (node (ref "C179") (pin "1") (pinfunction "1_1") (pintype "passive"))
      (node (ref "C180") (pin "1") (pinfunction "1_1") (pintype "passive"))
      (node (ref "C181") (pin "1") (pinfunction "1_1") (pintype "passive"))
      (node (ref "C182") (pin "1") (pinfunction "1_1") (pintype "passive"))
      (node (ref "C183") (pin "1") (pinfunction "1_1") (pintype "passive"))
      (node (ref "C184") (pin "1") (pinfunction "1_1") (pintype "passive"))
      (node (ref "C191") (pin "2") (pinfunction "2_2") (pintype "passive"))
      (node (ref "C192") (pin "2") (pinfunction "2_2") (pintype "passive"))
      (node (ref "C193") (pin "1") (pinfunction "1_1") (pintype "passive"))
      (node (ref "IC10") (pin "1") (pinfunction "E0_1") (pintype "input"))
      (node (ref "IC10") (pin "2") (pinfunction "E1_2") (pintype "input"))
      (node (ref "IC10") (pin "3") (pinfunction "E2_3") (pintype "input"))
      (node (ref "IC10") (pin "4") (pinfunction "VSS_4") (pintype "power_in"))
      (node (ref "IC10") (pin "7") (pinfunction "~{WC}_7") (pintype "input"))
      (node (ref "IC10") (pin "PAD") (pinfunction "PAD_PAD") (pintype "power_in"))
      (node (ref "IC11") (pin "4") (pinfunction "GND_4") (pintype "passive"))
      (node (ref "IC11") (pin "PAD") (pinfunction "PAD_PAD") (pintype "passive"))
      (node (ref "IC11A") (pin "4") (pinfunction "GND_4") (pintype "passive"))
      (node (ref "IC12") (pin "4") (pinfunction "SGND_4") (pintype "passive"))
      (node (ref "IC12") (pin "6") (pinfunction "PGND_6") (pintype "passive"))
      (node (ref "IC12") (pin "PAD") (pinfunction "PAD_(SGND)_PAD") (pintype "passive"))
      (node (ref "IC13") (pin "4") (pinfunction "SGND_4") (pintype "passive"))
      (node (ref "IC13") (pin "6") (pinfunction "PGND_6") (pintype "passive"))
      (node (ref "IC13") (pin "PAD") (pinfunction "PAD_(SGND)_PAD") (pintype "passive"))
      (node (ref "IC14") (pin "2") (pinfunction "GND_2") (pintype "passive"))
      (node (ref "IC14") (pin "PAD") (pinfunction "PAD_PAD") (pintype "passive"))
      (node (ref "IC7") (pin "1") (pinfunction "GND_1") (pintype "passive"))
      (node (ref "IC7") (pin "11") (pinfunction "GND_11") (pintype "passive"))
      (node (ref "IC7") (pin "12") (pinfunction "GND_12") (pintype "passive"))
      (node (ref "IC7") (pin "16") (pinfunction "GND_16") (pintype "passive"))
      (node (ref "IC7") (pin "19") (pinfunction "GND_19") (pintype "passive"))
      (node (ref "IC7") (pin "22") (pinfunction "SEL_22") (pintype "passive"))
      (node (ref "IC7") (pin "25") (pinfunction "GND_25") (pintype "passive"))
      (node (ref "IC7") (pin "7") (pinfunction "GND_7") (pintype "passive"))
      (node (ref "IC8") (pin "4") (pinfunction "GND_4") (pintype "passive"))
      (node (ref "IC8") (pin "5") (pinfunction "A2_5") (pintype "passive"))
      (node (ref "IC8") (pin "6") (pinfunction "A1_6") (pintype "passive"))
      (node (ref "IC8") (pin "7") (pinfunction "A0_7") (pintype "passive"))
      (node (ref "IC9") (pin "5") (pinfunction "GND_5") (pintype "power_in"))
      (node (ref "J8") (pin "2") (pinfunction "Y_2") (pintype "passive"))
      (node (ref "J9") (pin "2") (pinfunction "Y_2") (pintype "passive"))
      (node (ref "MECH11") (pin "1") (pinfunction "GND_1") (pintype "passive"))
      (node (ref "MECH12") (pin "1") (pinfunction "GND_1") (pintype "passive"))
      (node (ref "MECH13") (pin "1") (pinfunction "GND_1") (pintype "passive"))
      (node (ref "MECH14") (pin "1") (pinfunction "GND_1") (pintype "passive"))
      (node (ref "R63") (pin "1") (pinfunction "1_1") (pintype "passive"))
      (node (ref "R68") (pin "2") (pinfunction "2_2") (pintype "passive"))
      (node (ref "R74") (pin "1") (pinfunction "1_1") (pintype "passive"))
      (node (ref "R81") (pin "2") (pinfunction "2_2") (pintype "passive"))
      (node (ref "R82") (pin "1") (pinfunction "1_1") (pintype "passive"))
      (node (ref "R83") (pin "1") (pinfunction "1_1") (pintype "passive"))
      (node (ref "VT4") (pin "S") (pinfunction "S_S") (pintype "passive"))
      (node (ref "XO1") (pin "4") (pinfunction "GND_4") (pintype "passive"))
    )
    (net (code "26") (name "Net-(C148-Pad1)") (class "Default")
      (node (ref "C148") (pin "1") (pinfunction "1_1") (pintype "passive"))
      (node (ref "C149") (pin "2") (pinfunction "2_2") (pintype "passive"))
      (node (ref "R63") (pin "2") (pinfunction "2_2") (pintype "passive"))
    )
    (net (code "27") (name "Net-(C148-Pad2)") (class "Default")
      (node (ref "C148") (pin "2") (pinfunction "2_2") (pintype "passive"))
      (node (ref "R59") (pin "2") (pinfunction "2_2") (pintype "passive"))
      (node (ref "R62") (pin "2") (pinfunction "2_2") (pintype "passive"))
    )
    (net (code "28") (name "Net-(C153-Pad2)") (class "Default")
      (node (ref "C153") (pin "2") (pinfunction "2_2") (pintype "passive"))
      (node (ref "FR15") (pin "1") (pinfunction "1_1") (pintype "passive"))
      (node (ref "R60") (pin "1") (pinfunction "1_1") (pintype "passive"))
    )
    (net (code "29") (name "Net-(C172-Pad1)") (class "Default")
      (node (ref "C172") (pin "1") (pinfunction "1_1") (pintype "passive"))
      (node (ref "J10") (pin "2") (pinfunction "2_2") (pintype "passive"))
      (node (ref "R69") (pin "2") (pinfunction "2_2") (pintype "passive"))
      (node (ref "R71") (pin "2") (pinfunction "2_2") (pintype "passive"))
    )
    (net (code "30") (name "Net-(IC7-CLKin)") (class "Default")
      (node (ref "C149") (pin "1") (pinfunction "1_1") (pintype "passive"))
      (node (ref "IC7") (pin "21") (pinfunction "CLKin_21") (pintype "passive"))
    )
    (net (code "31") (name "Net-(IC7-CLKin*)") (class "Default")
      (node (ref "C156") (pin "2") (pinfunction "2_2") (pintype "passive"))
      (node (ref "IC7") (pin "20") (pinfunction "CLKin*_20") (pintype "passive"))
    )
    (net (code "32") (name "Net-(IC7-CLKout0)") (class "Default")
      (node (ref "IC7") (pin "3") (pinfunction "CLKout0_3") (pintype "passive"))
      (node (ref "R61") (pin "2") (pinfunction "2_2") (pintype "passive"))
    )
    (net (code "33") (name "Net-(IC7-CLKout1)") (class "Default")
      (node (ref "IC7") (pin "5") (pinfunction "CLKout1_5") (pintype "passive"))
      (node (ref "R65") (pin "2") (pinfunction "2_2") (pintype "passive"))
    )
    (net (code "34") (name "Net-(IC7-OE)") (class "Default")
      (node (ref "IC7") (pin "24") (pinfunction "OE_24") (pintype "passive"))
      (node (ref "R57") (pin "1") (pinfunction "1_1") (pintype "passive"))
    )
    (net (code "35") (name "Net-(IC9-VDD)") (class "Default")
      (node (ref "C163") (pin "1") (pinfunction "1_1") (pintype "passive"))
      (node (ref "FR17") (pin "2") (pinfunction "2_2") (pintype "passive"))
      (node (ref "IC9") (pin "4") (pinfunction "VDD_4") (pintype "power_in"))
    )
    (net (code "36") (name "Net-(IC9-VOUT)") (class "Default")
      (node (ref "IC9") (pin "6") (pinfunction "VOUT_6") (pintype "tri_state"))
      (node (ref "R67") (pin "2") (pinfunction "2_2") (pintype "passive"))
    )
    (net (code "37") (name "Net-(IC12-VCON)") (class "Default")
      (node (ref "C191") (pin "1") (pinfunction "1_1") (pintype "passive"))
      (node (ref "IC12") (pin "2") (pinfunction "VCON_2") (pintype "input"))
      (node (ref "R76") (pin "1") (pinfunction "1_1") (pintype "passive"))
      (node (ref "R82") (pin "2") (pinfunction "2_2") (pintype "passive"))
    )
    (net (code "38") (name "Net-(IC12-VREF)") (class "Default")
      (node (ref "IC12") (pin "8") (pinfunction "VREF_8") (pintype "output"))
      (node (ref "R76") (pin "2") (pinfunction "2_2") (pintype "passive"))
    )
    (net (code "39") (name "Net-(IC13-VCON)") (class "Default")
      (node (ref "C192") (pin "1") (pinfunction "1_1") (pintype "passive"))
      (node (ref "IC13") (pin "2") (pinfunction "VCON_2") (pintype "input"))
      (node (ref "R78") (pin "1") (pinfunction "1_1") (pintype "passive"))
      (node (ref "R83") (pin "2") (pinfunction "2_2") (pintype "passive"))
    )
    (net (code "40") (name "Net-(IC13-VREF)") (class "Default")
      (node (ref "IC13") (pin "8") (pinfunction "VREF_8") (pintype "output"))
      (node (ref "R78") (pin "2") (pinfunction "2_2") (pintype "passive"))
    )
    (net (code "41") (name "Net-(IC14-ADJ)") (class "Default")
      (node (ref "IC14") (pin "5") (pinfunction "ADJ_5") (pintype "input"))
      (node (ref "R80") (pin "1") (pinfunction "1_1") (pintype "passive"))
      (node (ref "R81") (pin "1") (pinfunction "1_1") (pintype "passive"))
    )
    (net (code "42") (name "Net-(IC14-PG)") (class "Default")
      (node (ref "C183") (pin "2") (pinfunction "2_2") (pintype "passive"))
      (node (ref "IC14") (pin "3") (pinfunction "PG_3") (pintype "output"))
    )
    (net (code "43") (name "Net-(IC14-Vout)") (class "Default")
      (node (ref "IC14") (pin "4") (pinfunction "Vout_4") (pintype "output"))
      (node (ref "R79") (pin "1") (pinfunction "1_1") (pintype "passive"))
      (node (ref "R80") (pin "2") (pinfunction "2_2") (pintype "passive"))
    )
    (net (code "44") (name "Net-(J10-Pad1)") (class "Default")
      (node (ref "J10") (pin "1") (pinfunction "1_1") (pintype "passive"))
      (node (ref "R74") (pin "2") (pinfunction "2_2") (pintype "passive"))
      (node (ref "VT4") (pin "D") (pinfunction "D_D") (pintype "passive"))
    )
    (net (code "45") (name "Net-(LED1-Pad3)") (class "Default")
      (node (ref "LED1") (pin "3") (pinfunction "3_3") (pintype "power_in"))
      (node (ref "R70") (pin "1") (pinfunction "1_1") (pintype "passive"))
    )
    (net (code "46") (name "Net-(LED1-Pad4)") (class "Default")
      (node (ref "LED1") (pin "4") (pinfunction "4_4") (pintype "power_in"))
      (node (ref "R72") (pin "1") (pinfunction "1_1") (pintype "passive"))
    )
    (net (code "47") (name "Net-(LED2-PadC1)") (class "Default")
      (node (ref "LED2") (pin "C1") (pinfunction "C1_C1") (pintype "power_in"))
      (node (ref "R75") (pin "1") (pinfunction "1_1") (pintype "passive"))
    )
    (net (code "48") (name "Net-(LED2-PadC2)") (class "Default")
      (node (ref "LED2") (pin "C2") (pinfunction "C2_C2") (pintype "power_in"))
      (node (ref "R73") (pin "1") (pinfunction "1_1") (pintype "passive"))
    )
    (net (code "49") (name "Net-(XO1-RF_OUT)") (class "Default")
      (node (ref "R59") (pin "1") (pinfunction "1_1") (pintype "passive"))
      (node (ref "XO1") (pin "6") (pinfunction "RF_OUT_6") (pintype "output"))
    )
    (net (code "50") (name "Net-(XO1-VCC)") (class "Default")
      (node (ref "C155") (pin "2") (pinfunction "2_2") (pintype "passive"))
      (node (ref "FR15") (pin "2") (pinfunction "2_2") (pintype "passive"))
      (node (ref "XO1") (pin "9") (pinfunction "VCC_9") (pintype "power_in"))
    )
    (net (code "51") (name "Net-(XO1-VC_FILTER)") (class "Default")
      (node (ref "C151") (pin "2") (pinfunction "2_2") (pintype "passive"))
      (node (ref "XO1") (pin "7") (pinfunction "VC_FILTER_7") (pintype "input"))
    )
    (net (code "52") (name "VCC1P8") (class "Default")
      (node (ref "C174") (pin "1") (pinfunction "1_1") (pintype "passive"))
      (node (ref "C182") (pin "2") (pinfunction "2_2") (pintype "passive"))
      (node (ref "FR16") (pin "1") (pinfunction "1_1") (pintype "passive"))
      (node (ref "FR20") (pin "1") (pinfunction "1_1") (pintype "passive"))
      (node (ref "IC11") (pin "8") (pinfunction "VCC_8") (pintype "power_in"))
      (node (ref "IC11A") (pin "8") (pinfunction "VCC_8") (pintype "passive"))
      (node (ref "IC13") (pin "3") (pinfunction "FB_3") (pintype "input"))
      (node (ref "IC13") (pin "5") (pinfunction "VOUT_5") (pintype "output"))
      (node (ref "R58") (pin "2") (pinfunction "2_2") (pintype "passive"))
      (node (ref "R84") (pin "2") (pinfunction "2_2") (pintype "passive"))
    )
    (net (code "53") (name "VCC1P8_LMS") (class "Default")
      (node (ref "C175") (pin "2") (pinfunction "2_2") (pintype "passive"))
      (node (ref "FR20") (pin "2") (pinfunction "2_2") (pintype "passive"))
    )
    (net (code "54") (name "VCC3P3") (class "Default")
      (node (ref "C150") (pin "1") (pinfunction "1_1") (pintype "passive"))
      (node (ref "C162") (pin "1") (pinfunction "1_1") (pintype "passive"))
      (node (ref "C177") (pin "2") (pinfunction "2_2") (pintype "passive"))
      (node (ref "C178") (pin "2") (pinfunction "2_2") (pintype "passive"))
      (node (ref "FR22") (pin "1") (pinfunction "1_1") (pintype "passive"))
      (node (ref "IC10") (pin "8") (pinfunction "VCC_8") (pintype "power_in"))
      (node (ref "IC12") (pin "3") (pinfunction "FB_3") (pintype "input"))
      (node (ref "IC12") (pin "5") (pinfunction "VOUT_5") (pintype "output"))
      (node (ref "IC14") (pin "1") (pinfunction "EN_1") (pintype "input"))
      (node (ref "IC14") (pin "6") (pinfunction "Vin_6") (pintype "input"))
      (node (ref "IC8") (pin "8") (pinfunction "VCC_8") (pintype "passive"))
      (node (ref "LED1") (pin "1") (pinfunction "1_1") (pintype "power_in"))
      (node (ref "LED1") (pin "2") (pinfunction "2_2") (pintype "power_in"))
      (node (ref "LED2") (pin "A") (pinfunction "A_A") (pintype "power_in"))
      (node (ref "R64") (pin "1") (pinfunction "1_1") (pintype "passive"))
      (node (ref "R66") (pin "1") (pinfunction "1_1") (pintype "passive"))
      (node (ref "R71") (pin "1") (pinfunction "1_1") (pintype "passive"))
      (node (ref "R77") (pin "1") (pinfunction "1_1") (pintype "passive"))
    )
    (net (code "55") (name "VCC3P3_CLK") (class "Default")
      (node (ref "C184") (pin "2") (pinfunction "2_2") (pintype "passive"))
      (node (ref "FR17") (pin "1") (pinfunction "1_1") (pintype "passive"))
      (node (ref "FR19") (pin "1") (pinfunction "1_1") (pintype "passive"))
      (node (ref "FR22") (pin "2") (pinfunction "2_2") (pintype "passive"))
      (node (ref "R60") (pin "2") (pinfunction "2_2") (pintype "passive"))
    )
    (net (code "56") (name "VCC5P0_USB") (class "Default")
      (node (ref "C176") (pin "2") (pinfunction "2_2") (pintype "passive"))
      (node (ref "C181") (pin "2") (pinfunction "2_2") (pintype "passive"))
      (node (ref "IC12") (pin "7") (pinfunction "VIN_7") (pintype "input"))
      (node (ref "IC13") (pin "1") (pinfunction "EN_1") (pintype "input"))
      (node (ref "IC13") (pin "7") (pinfunction "VIN_7") (pintype "input"))
      (node (ref "R69") (pin "1") (pinfunction "1_1") (pintype "passive"))
      (node (ref "R94") (pin "1") (pinfunction "1_1") (pintype "passive"))
    )
    (net (code "57") (name "VDIO_LMS") (class "Default")
      (node (ref "C180") (pin "2") (pinfunction "2_2") (pintype "passive"))
      (node (ref "FR21") (pin "2") (pinfunction "2_2") (pintype "passive"))
    )
    (net (code "58") (name "VDIO_LMS_FPGA") (class "Default")
      (node (ref "C179") (pin "2") (pinfunction "2_2") (pintype "passive"))
      (node (ref "FR18") (pin "1") (pinfunction "1_1") (pintype "passive"))
      (node (ref "FR21") (pin "1") (pinfunction "1_1") (pintype "passive"))
      (node (ref "R77") (pin "2") (pinfunction "2_2") (pintype "passive"))
      (node (ref "R79") (pin "2") (pinfunction "2_2") (pintype "passive"))
    )
    (net (code "59") (name "VDIO_LMS_LMK") (class "Default")
      (node (ref "C164") (pin "2") (pinfunction "2_2") (pintype "passive"))
      (node (ref "C165") (pin "2") (pinfunction "2_2") (pintype "passive"))
      (node (ref "C166") (pin "2") (pinfunction "2_2") (pintype "passive"))
      (node (ref "C167") (pin "2") (pinfunction "2_2") (pintype "passive"))
      (node (ref "FR18") (pin "2") (pinfunction "2_2") (pintype "passive"))
      (node (ref "IC7") (pin "14") (pinfunction "Vddo_14") (pintype "passive"))
      (node (ref "IC7") (pin "18") (pinfunction "Vddo_18") (pintype "passive"))
    )
    (net (code "60") (name "unconnected-(FAN1-STANDS-Pad1)") (class "Default")
      (node (ref "FAN1") (pin "1") (pinfunction "STANDS_1") (pintype "passive+no_connect"))
    )
    (net (code "61") (name "unconnected-(IC7-CLKout3-Pad15)") (class "Default")
      (node (ref "IC7") (pin "15") (pinfunction "CLKout3_15") (pintype "passive+no_connect"))
    )
    (net (code "62") (name "unconnected-(IC7-OSCin-Pad9)") (class "Default")
      (node (ref "IC7") (pin "9") (pinfunction "OSCin_9") (pintype "passive+no_connect"))
    )
    (net (code "63") (name "unconnected-(IC7-OSCout-Pad10)") (class "Default")
      (node (ref "IC7") (pin "10") (pinfunction "OSCout_10") (pintype "passive+no_connect"))
    )
    (net (code "64") (name "unconnected-(MECH16-PadMH1)") (class "Default")
      (node (ref "MECH16") (pin "MH1") (pinfunction "MH1_MH1") (pintype "passive+no_connect"))
    )
    (net (code "65") (name "unconnected-(MECH17-PadMH1)") (class "Default")
      (node (ref "MECH17") (pin "MH1") (pinfunction "MH1_MH1") (pintype "passive+no_connect"))
    )
    (net (code "66") (name "unconnected-(MECH18-PadMH1)") (class "Default")
      (node (ref "MECH18") (pin "MH1") (pinfunction "MH1_MH1") (pintype "passive+no_connect"))
    )
    (net (code "67") (name "unconnected-(MECH19-PadMH1)") (class "Default")
      (node (ref "MECH19") (pin "MH1") (pinfunction "MH1_MH1") (pintype "passive+no_connect"))
    )
    (net (code "68") (name "unconnected-(MECH20-PadMH1)") (class "Default")
      (node (ref "MECH20") (pin "MH1") (pinfunction "MH1_MH1") (pintype "passive+no_connect"))
    )
    (net (code "69") (name "unconnected-(MECH21-PadMH1)") (class "Default")
      (node (ref "MECH21") (pin "MH1") (pinfunction "MH1_MH1") (pintype "passive+no_connect"))
    )
    (net (code "70") (name "unconnected-(XO1-NC-Pad2)") (class "Default")
      (node (ref "XO1") (pin "2") (pinfunction "NC_2") (pintype "passive+no_connect"))
    )
    (net (code "71") (name "unconnected-(XO1-NC-Pad3)") (class "Default")
      (node (ref "XO1") (pin "3") (pinfunction "NC_3") (pintype "passive+no_connect"))
    )
    (net (code "72") (name "unconnected-(XO1-NC-Pad5)") (class "Default")
      (node (ref "XO1") (pin "5") (pinfunction "NC_5") (pintype "passive+no_connect"))
    )
    (net (code "73") (name "unconnected-(XO1-NC-Pad8)") (class "Default")
      (node (ref "XO1") (pin "8") (pinfunction "NC_8") (pintype "passive+no_connect"))
    )
    (net (code "74") (name "unconnected-(XO1-NC-Pad10)") (class "Default")
      (node (ref "XO1") (pin "10") (pinfunction "NC_10") (pintype "passive+no_connect"))
    )
  )
)
